# Morpheus_MCU.net
KiCad netlist of a schematic drawn in Altium Designer
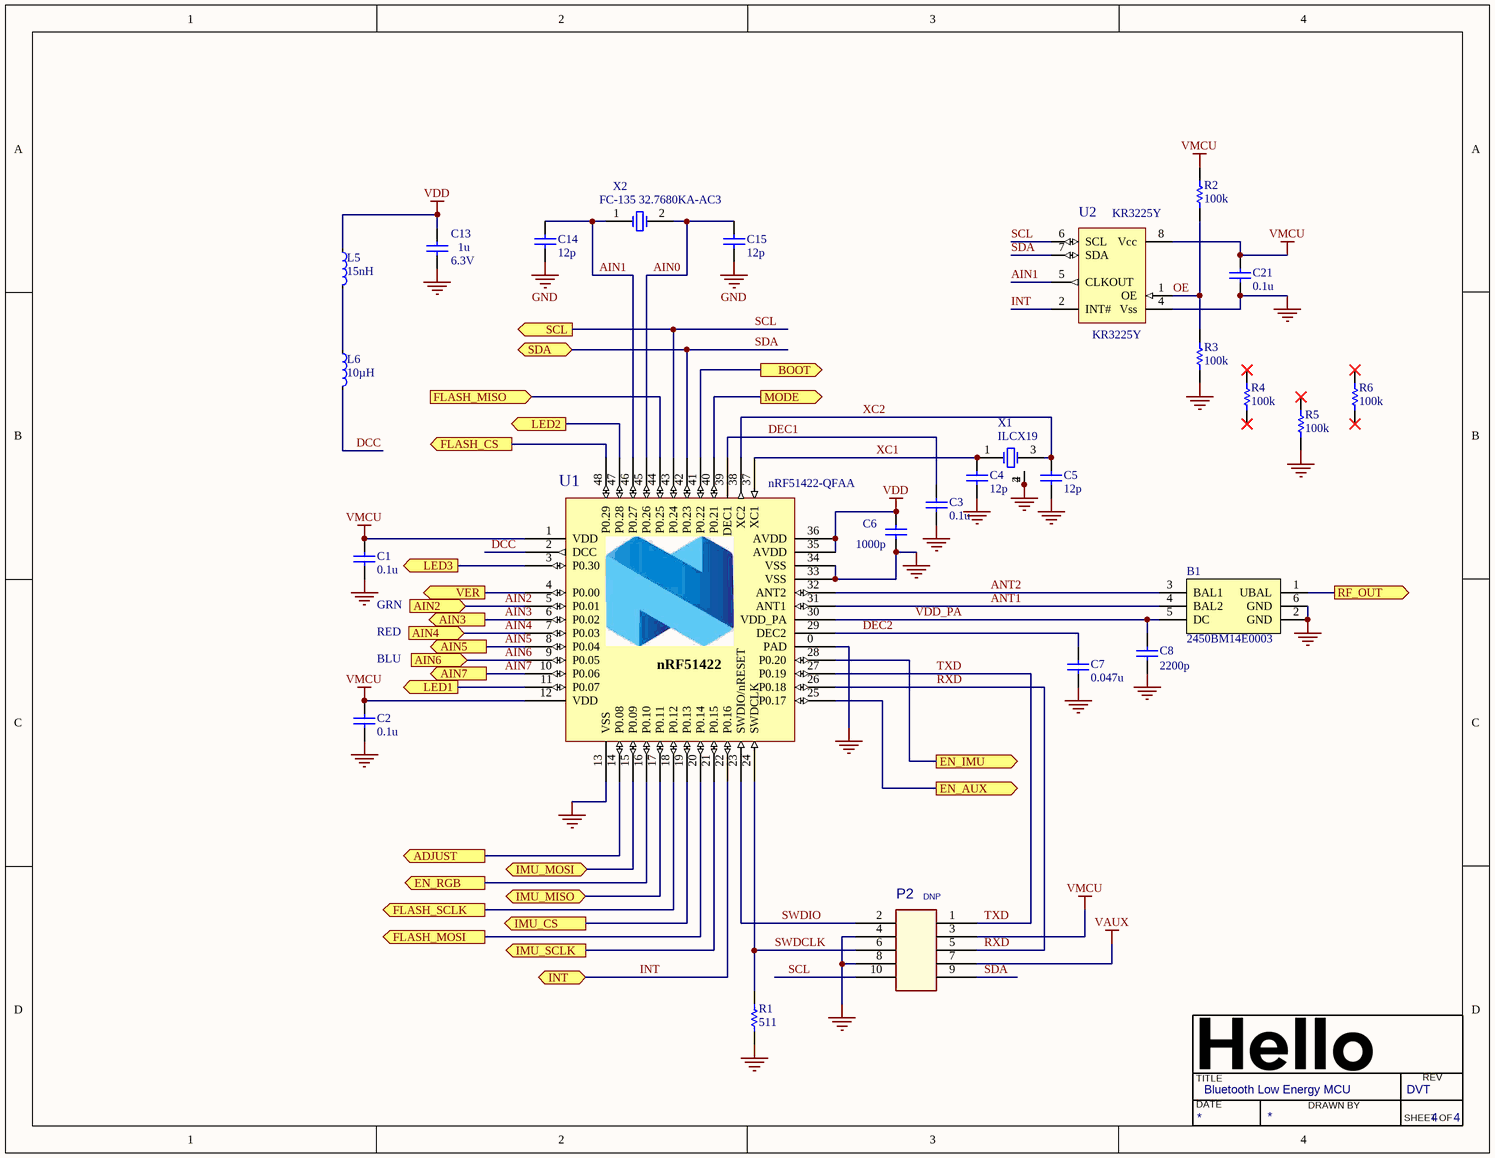
[diagram p0: Morpheus_MCU.SchDoc]

(export (version "E")
  (design (tool "Eeschema 10.0.6"))
  (components
    (comp (ref "B1")
      (value "2450BM14E0003")
      (footprint "DFN50P160X80X70-6N")
      (description "2.45 GHz Impedance Matched Balun-Filter")
      (libsource (lib "HelloDVT") (part "2450BM14E0003"))
    )
    (comp (ref "C1")
      (value "0.1u")
      (footprint "CAP0402_SENSE_DVT")
      (description "Chip capacitor")
      (fields (field (name "TOLERANCE") "10%") (field (name "VOLTAGE") "50V"))
      (libsource (lib "Hello") (part "C_0.1u_10_50_X7R_0402"))
    )
    (comp (ref "C2")
      (value "0.1u")
      (footprint "CAP0402_SENSE_DVT")
      (description "Chip capacitor")
      (fields (field (name "TOLERANCE") "10%") (field (name "VOLTAGE") "50V"))
      (libsource (lib "Hello") (part "C_0.1u_10_50_X7R_0402"))
    )
    (comp (ref "C3")
      (value "0.1u")
      (footprint "CAP0402_SENSE_DVT")
      (description "Chip capacitor")
      (fields (field (name "TOLERANCE") "10%") (field (name "VOLTAGE") "50V"))
      (libsource (lib "Hello") (part "C_0.1u_10_50_X7R_0402"))
    )
    (comp (ref "C4")
      (value "12p")
      (footprint "CAP0402_SENSE_DVT")
      (description "Chip capacitor")
      (fields (field (name "TOLERANCE") "5%") (field (name "VOLTAGE") "50V"))
      (libsource (lib "Hello") (part "C_12p_5_50_C0G_0402"))
    )
    (comp (ref "C5")
      (value "12p")
      (footprint "CAP0402_SENSE_DVT")
      (description "Chip capacitor")
      (fields (field (name "TOLERANCE") "5%") (field (name "VOLTAGE") "50V"))
      (libsource (lib "Hello") (part "C_12p_5_50_C0G_0402"))
    )
    (comp (ref "C6")
      (value "1000p")
      (footprint "CAP0402_SENSE_DVT")
      (description "Chip capacitor")
      (fields (field (name "TOLERANCE") "10%") (field (name "VOLTAGE") "25V"))
      (libsource (lib "Hello") (part "C_1000p_10_25_X7R_0201"))
    )
    (comp (ref "C7")
      (value "0.047u")
      (footprint "CAP0402_SENSE_DVT")
      (description "Chip capacitor")
      (fields (field (name "TOLERANCE") "10%") (field (name "VOLTAGE") "16V"))
      (libsource (lib "Hello") (part "C_0.047u_10_16_X5R_0201"))
    )
    (comp (ref "C8")
      (value "2200p")
      (footprint "CAP0402_SENSE_DVT")
      (description "Chip capacitor")
      (fields (field (name "TOLERANCE") "5 %") (field (name "VOLTAGE") "16V"))
      (libsource (lib "Hello") (part "C_2200p_5_16_X7R_0201"))
    )
    (comp (ref "C13")
      (value "1u")
      (footprint "CAP0402_SENSE_DVT")
      (description "Chip capacitor")
      (fields (field (name "TOLERANCE") "10%") (field (name "VOLTAGE") "6.3V"))
      (libsource (lib "Hello") (part "C_1u_10_6.3_X5R_0402"))
    )
    (comp (ref "C14")
      (value "12p")
      (footprint "CAP0402_SENSE_DVT")
      (description "Chip capacitor")
      (fields (field (name "TOLERANCE") "5%") (field (name "VOLTAGE") "50V"))
      (libsource (lib "Hello") (part "C_12p_5_50_C0G_0402"))
    )
    (comp (ref "C15")
      (value "12p")
      (footprint "CAP0402_SENSE_DVT")
      (description "Chip capacitor")
      (fields (field (name "TOLERANCE") "5%") (field (name "VOLTAGE") "50V"))
      (libsource (lib "Hello") (part "C_12p_5_50_C0G_0402"))
    )
    (comp (ref "C21")
      (value "0.1u")
      (footprint "CAP0402_SENSE_DVT")
      (description "Chip capacitor")
      (fields (field (name "TOLERANCE") "10%") (field (name "VOLTAGE") "50V"))
      (libsource (lib "Hello") (part "C_0.1u_10_50_X7R_0402"))
    )
    (comp (ref "L5")
      (value "15nH")
      (footprint "INDC1005X04L")
      (description "Inductor, 320mA, ±5%")
      (fields
        (field (name "PART NUMBER") "L0402-15n")
        (field (name "MANUFACTURER") "Taiyo Yuden")
        (field (name "PUBLISHER") "Nordic Semiconductor")
      )
      (libsource (lib "Nordic Passive DB") (part "IND"))
    )
    (comp (ref "L6")
      (value "10µH")
      (footprint "INDC1608X06L")
      (description "Inductor, 80mA, ±10%")
      (fields
        (field (name "PART NUMBER") "L0603-10µ")
        (field (name "MANUFACTURER") "Taiyo Yuden")
        (field (name "PUBLISHER") "Nordic Semiconductor")
      )
      (libsource (lib "Nordic Passive DB") (part "IND"))
    )
    (comp (ref "P2")
      (value "DNP")
      (footprint "HDR1.27-2X5-N")
      (libsource (lib "Morpheus_LED") (part "CON10A"))
    )
    (comp (ref "R1")
      (value "511")
      (footprint "RES0402_SENSE_DVT")
      (description "Chip Resistor")
      (fields (field (name "TOLERANCE") "1 %") (field (name "POWER") "0.1 W"))
      (libsource (lib "Hello") (part "R_511_1_0.1_0402"))
    )
    (comp (ref "R2")
      (value "100k")
      (footprint "RES0402_SENSE_DVT")
      (description "Chip Resistor")
      (fields (field (name "TOLERANCE") "1 %") (field (name "POWER") "0.1 W"))
      (libsource (lib "Hello") (part "R_100k_1_0.1_0402"))
    )
    (comp (ref "R3")
      (value "100k")
      (footprint "RES0402_SENSE_DVT")
      (description "Chip Resistor")
      (fields (field (name "TOLERANCE") "1 %") (field (name "POWER") "0.1 W"))
      (libsource (lib "Hello") (part "R_100k_1_0.1_0402"))
    )
    (comp (ref "R4")
      (value "100k")
      (footprint "RES0402_SENSE_DVT")
      (description "Chip Resistor")
      (fields (field (name "TOLERANCE") "1 %") (field (name "POWER") "0.1 W"))
      (libsource (lib "Hello") (part "R_100k_1_0.1_0402"))
    )
    (comp (ref "R5")
      (value "100k")
      (footprint "RES0402_SENSE_DVT")
      (description "Chip Resistor")
      (fields (field (name "TOLERANCE") "1 %") (field (name "POWER") "0.1 W"))
      (libsource (lib "Hello") (part "R_100k_1_0.1_0402"))
    )
    (comp (ref "R6")
      (value "100k")
      (footprint "RES0402_SENSE_DVT")
      (description "Chip Resistor")
      (fields (field (name "TOLERANCE") "1 %") (field (name "POWER") "0.1 W"))
      (libsource (lib "Hello") (part "R_100k_1_0.1_0402"))
    )
    (comp (ref "U1")
      (value "nRF51422-QFAA")
      (footprint "VQFN40P600X600X100-48")
      (description "Multi-protocol Bluetooth Low Energy, ANT and 2.4GHz proprietary system-on-chip")
      (libsource (lib "Hello") (part "nRF51422_QFAA"))
    )
    (comp (ref "U2")
      (value "KR3225Y")
      (footprint "8-CLCC-KYOCERO")
      (description "Kyocero I2C RTC w/ Crystal")
      (fields (field (name "PN") "KR3225Y"))
      (libsource (lib "Smith_top") (part "KR3225Y32768DGR"))
    )
    (comp (ref "X1")
      (value "ILCX19")
      (footprint "ILCX19")
      (description "ILSI ILCX19 Crystal Oscillator")
      (libsource (lib "Smith_top") (part "ILCX19"))
    )
    (comp (ref "X2")
      (value "FC-135 32.7680KA-AC3")
      (footprint "Epson_FC-135")
      (description "Epson 32kHz crystal, 9pF")
      (libsource (lib "Hello") (part "Espon_FC-135 32.7680KA-AC3"))
    )
  )
  (nets
    (net (code "1") (name "/ADJUST") (class "Default")
      (node (ref "U1") (pin "14") (pinfunction "P0.08_14") (pintype "bidirectional"))
    )
    (net (code "2") (name "/AIN0") (class "Default")
      (node (ref "C15") (pin "2") (pinfunction "2_2") (pintype "passive"))
      (node (ref "U1") (pin "45") (pinfunction "P0.26_45") (pintype "bidirectional"))
      (node (ref "X2") (pin "2") (pinfunction "2_2") (pintype "passive"))
    )
    (net (code "3") (name "/AIN1") (class "Default")
      (node (ref "C14") (pin "2") (pinfunction "2_2") (pintype "passive"))
      (node (ref "U1") (pin "46") (pinfunction "P0.27_46") (pintype "bidirectional"))
      (node (ref "U2") (pin "5") (pinfunction "CLKOUT_5") (pintype "output"))
      (node (ref "X2") (pin "1") (pinfunction "1_1") (pintype "passive"))
    )
    (net (code "4") (name "/AIN2") (class "Default")
      (node (ref "U1") (pin "5") (pinfunction "P0.01_5") (pintype "bidirectional"))
    )
    (net (code "5") (name "/AIN3") (class "Default")
      (node (ref "U1") (pin "6") (pinfunction "P0.02_6") (pintype "bidirectional"))
    )
    (net (code "6") (name "/AIN4") (class "Default")
      (node (ref "U1") (pin "7") (pinfunction "P0.03_7") (pintype "bidirectional"))
    )
    (net (code "7") (name "/AIN5") (class "Default")
      (node (ref "U1") (pin "8") (pinfunction "P0.04_8") (pintype "bidirectional"))
    )
    (net (code "8") (name "/AIN6") (class "Default")
      (node (ref "U1") (pin "9") (pinfunction "P0.05_9") (pintype "bidirectional"))
    )
    (net (code "9") (name "/AIN7") (class "Default")
      (node (ref "U1") (pin "10") (pinfunction "P0.06_10") (pintype "bidirectional"))
    )
    (net (code "10") (name "/ANT1") (class "Default")
      (node (ref "B1") (pin "4") (pinfunction "BAL2_4") (pintype "passive"))
      (node (ref "U1") (pin "31") (pinfunction "ANT1_31") (pintype "bidirectional"))
    )
    (net (code "11") (name "/ANT2") (class "Default")
      (node (ref "B1") (pin "3") (pinfunction "BAL1_3") (pintype "passive"))
      (node (ref "U1") (pin "32") (pinfunction "ANT2_32") (pintype "bidirectional"))
    )
    (net (code "12") (name "/BOOT") (class "Default")
      (node (ref "U1") (pin "41") (pinfunction "P0.22_41") (pintype "bidirectional"))
    )
    (net (code "13") (name "/DCC") (class "Default")
      (node (ref "L6") (pin "2") (pinfunction "2_2") (pintype "passive"))
      (node (ref "U1") (pin "2") (pinfunction "DCC_2") (pintype "output"))
    )
    (net (code "14") (name "/DEC1") (class "Default")
      (node (ref "C3") (pin "2") (pinfunction "2_2") (pintype "passive"))
      (node (ref "U1") (pin "39") (pinfunction "DEC1_39") (pintype "power_in"))
    )
    (net (code "15") (name "/DEC2") (class "Default")
      (node (ref "C7") (pin "2") (pinfunction "2_2") (pintype "passive"))
      (node (ref "U1") (pin "29") (pinfunction "DEC2_29") (pintype "power_in"))
    )
    (net (code "16") (name "/EN_AUX") (class "Default")
      (node (ref "U1") (pin "25") (pinfunction "P0.17_25") (pintype "bidirectional"))
    )
    (net (code "17") (name "/EN_IMU") (class "Default")
      (node (ref "U1") (pin "28") (pinfunction "P0.20_28") (pintype "bidirectional"))
    )
    (net (code "18") (name "/EN_RGB") (class "Default")
      (node (ref "U1") (pin "16") (pinfunction "P0.10_16") (pintype "bidirectional"))
    )
    (net (code "19") (name "/FLASH_CS") (class "Default")
      (node (ref "U1") (pin "48") (pinfunction "P0.29_48") (pintype "bidirectional"))
    )
    (net (code "20") (name "/FLASH_MISO") (class "Default")
      (node (ref "U1") (pin "44") (pinfunction "P0.25_44") (pintype "bidirectional"))
    )
    (net (code "21") (name "/FLASH_MOSI") (class "Default")
      (node (ref "U1") (pin "20") (pinfunction "P0.14_20") (pintype "bidirectional"))
    )
    (net (code "22") (name "/FLASH_SCLK") (class "Default")
      (node (ref "U1") (pin "18") (pinfunction "P0.12_18") (pintype "bidirectional"))
    )
    (net (code "23") (name "/IMU_CS") (class "Default")
      (node (ref "U1") (pin "19") (pinfunction "P0.13_19") (pintype "bidirectional"))
    )
    (net (code "24") (name "/IMU_MISO") (class "Default")
      (node (ref "U1") (pin "17") (pinfunction "P0.11_17") (pintype "bidirectional"))
    )
    (net (code "25") (name "/IMU_MOSI") (class "Default")
      (node (ref "U1") (pin "15") (pinfunction "P0.09_15") (pintype "bidirectional"))
    )
    (net (code "26") (name "/IMU_SCLK") (class "Default")
      (node (ref "U1") (pin "21") (pinfunction "P0.15_21") (pintype "bidirectional"))
    )
    (net (code "27") (name "/INT") (class "Default")
      (node (ref "U1") (pin "22") (pinfunction "P0.16_22") (pintype "bidirectional"))
      (node (ref "U2") (pin "2") (pinfunction "INT#_2") (pintype "open_emitter"))
    )
    (net (code "28") (name "/LED1") (class "Default")
      (node (ref "U1") (pin "11") (pinfunction "P0.07_11") (pintype "bidirectional"))
    )
    (net (code "29") (name "/LED2") (class "Default")
      (node (ref "U1") (pin "47") (pinfunction "P0.28_47") (pintype "bidirectional"))
    )
    (net (code "30") (name "/LED3") (class "Default")
      (node (ref "U1") (pin "3") (pinfunction "P0.30_3") (pintype "bidirectional"))
    )
    (net (code "31") (name "/MODE") (class "Default")
      (node (ref "U1") (pin "40") (pinfunction "P0.21_40") (pintype "bidirectional"))
    )
    (net (code "32") (name "/OE") (class "Default")
      (node (ref "R2") (pin "1") (pinfunction "1_1") (pintype "passive"))
      (node (ref "R3") (pin "2") (pinfunction "2_2") (pintype "passive"))
      (node (ref "U2") (pin "1") (pinfunction "OE_1") (pintype "input"))
    )
    (net (code "33") (name "/RF_OUT") (class "Default")
      (node (ref "B1") (pin "1") (pinfunction "UBAL_1") (pintype "passive"))
    )
    (net (code "34") (name "/RXD") (class "Default")
      (node (ref "P2") (pin "5") (pinfunction "5_5") (pintype "passive"))
      (node (ref "U1") (pin "26") (pinfunction "P0.18_26") (pintype "bidirectional"))
    )
    (net (code "35") (name "/SCL") (class "Default")
      (node (ref "P2") (pin "10") (pinfunction "10_10") (pintype "passive"))
      (node (ref "U1") (pin "43") (pinfunction "P0.24_43") (pintype "bidirectional"))
      (node (ref "U2") (pin "6") (pinfunction "SCL_6") (pintype "bidirectional"))
    )
    (net (code "36") (name "/SDA") (class "Default")
      (node (ref "P2") (pin "9") (pinfunction "9_9") (pintype "passive"))
      (node (ref "U1") (pin "42") (pinfunction "P0.23_42") (pintype "bidirectional"))
      (node (ref "U2") (pin "7") (pinfunction "SDA_7") (pintype "bidirectional"))
    )
    (net (code "37") (name "/SWDCLK") (class "Default")
      (node (ref "P2") (pin "6") (pinfunction "6_6") (pintype "passive"))
      (node (ref "R1") (pin "2") (pinfunction "2_2") (pintype "passive"))
      (node (ref "U1") (pin "24") (pinfunction "SWDCLK_24") (pintype "input"))
    )
    (net (code "38") (name "/SWDIO") (class "Default")
      (node (ref "P2") (pin "2") (pinfunction "2_2") (pintype "passive"))
      (node (ref "U1") (pin "23") (pinfunction "SWDIO/nRESET_23") (pintype "input"))
    )
    (net (code "39") (name "/TXD") (class "Default")
      (node (ref "P2") (pin "1") (pinfunction "1_1") (pintype "passive"))
      (node (ref "U1") (pin "27") (pinfunction "P0.19_27") (pintype "bidirectional"))
    )
    (net (code "40") (name "/VDD_PA") (class "Default")
      (node (ref "B1") (pin "5") (pinfunction "DC_5") (pintype "passive"))
      (node (ref "C8") (pin "2") (pinfunction "2_2") (pintype "passive"))
      (node (ref "U1") (pin "30") (pinfunction "VDD_PA_30") (pintype "power_in"))
    )
    (net (code "41") (name "/VER") (class "Default")
      (node (ref "U1") (pin "4") (pinfunction "P0.00_4") (pintype "bidirectional"))
    )
    (net (code "42") (name "/XC1") (class "Default")
      (node (ref "C4") (pin "2") (pinfunction "2_2") (pintype "passive"))
      (node (ref "U1") (pin "37") (pinfunction "XC1_37") (pintype "input"))
      (node (ref "X1") (pin "1") (pinfunction "XTAL1_1") (pintype "passive"))
    )
    (net (code "43") (name "/XC2") (class "Default")
      (node (ref "C5") (pin "2") (pinfunction "2_2") (pintype "passive"))
      (node (ref "U1") (pin "38") (pinfunction "XC2_38") (pintype "output"))
      (node (ref "X1") (pin "3") (pinfunction "XTAL2_3") (pintype "passive"))
    )
    (net (code "44") (name "GND") (class "Default")
      (node (ref "B1") (pin "2") (pinfunction "GND_2") (pintype "passive"))
      (node (ref "B1") (pin "6") (pinfunction "GND_6") (pintype "power_in"))
      (node (ref "C1") (pin "1") (pinfunction "1_1") (pintype "passive"))
      (node (ref "C13") (pin "1") (pinfunction "1_1") (pintype "passive"))
      (node (ref "C14") (pin "1") (pinfunction "1_1") (pintype "passive"))
      (node (ref "C15") (pin "1") (pinfunction "1_1") (pintype "passive"))
      (node (ref "C2") (pin "1") (pinfunction "1_1") (pintype "passive"))
      (node (ref "C21") (pin "1") (pinfunction "1_1") (pintype "passive"))
      (node (ref "C3") (pin "1") (pinfunction "1_1") (pintype "passive"))
      (node (ref "C4") (pin "1") (pinfunction "1_1") (pintype "passive"))
      (node (ref "C5") (pin "1") (pinfunction "1_1") (pintype "passive"))
      (node (ref "C6") (pin "1") (pinfunction "1_1") (pintype "passive"))
      (node (ref "C7") (pin "1") (pinfunction "1_1") (pintype "passive"))
      (node (ref "C8") (pin "1") (pinfunction "1_1") (pintype "passive"))
      (node (ref "P2") (pin "4") (pinfunction "4_4") (pintype "passive"))
      (node (ref "P2") (pin "8") (pinfunction "8_8") (pintype "passive"))
      (node (ref "R1") (pin "1") (pinfunction "1_1") (pintype "passive"))
      (node (ref "R3") (pin "1") (pinfunction "1_1") (pintype "passive"))
      (node (ref "R5") (pin "1") (pinfunction "1_1") (pintype "passive"))
      (node (ref "U1") (pin "0") (pinfunction "PAD_0") (pintype "power_in"))
      (node (ref "U1") (pin "13") (pinfunction "VSS_13") (pintype "power_in"))
      (node (ref "U1") (pin "33") (pinfunction "VSS_33") (pintype "power_in"))
      (node (ref "U1") (pin "34") (pinfunction "VSS_34") (pintype "power_in"))
      (node (ref "U2") (pin "4") (pinfunction "Vss_4") (pintype "power_in"))
      (node (ref "X1") (pin "2") (pinfunction "GND1_2") (pintype "passive"))
      (node (ref "X1") (pin "4") (pinfunction "XTAL2_4") (pintype "passive"))
    )
    (net (code "45") (name "Net-(L5-Pad2)") (class "Default")
      (node (ref "L5") (pin "2") (pinfunction "2_2") (pintype "passive"))
      (node (ref "L6") (pin "1") (pinfunction "1_1") (pintype "passive"))
    )
    (net (code "46") (name "VAUX") (class "Default")
      (node (ref "P2") (pin "7") (pinfunction "7_7") (pintype "passive"))
    )
    (net (code "47") (name "VDD") (class "Default")
      (node (ref "C13") (pin "2") (pinfunction "2_2") (pintype "passive"))
      (node (ref "C6") (pin "2") (pinfunction "2_2") (pintype "passive"))
      (node (ref "L5") (pin "1") (pinfunction "1_1") (pintype "passive"))
      (node (ref "U1") (pin "35") (pinfunction "AVDD_35") (pintype "power_in"))
      (node (ref "U1") (pin "36") (pinfunction "AVDD_36") (pintype "power_in"))
    )
    (net (code "48") (name "VMCU") (class "Default")
      (node (ref "C1") (pin "2") (pinfunction "2_2") (pintype "passive"))
      (node (ref "C2") (pin "2") (pinfunction "2_2") (pintype "passive"))
      (node (ref "C21") (pin "2") (pinfunction "2_2") (pintype "passive"))
      (node (ref "P2") (pin "3") (pinfunction "3_3") (pintype "passive"))
      (node (ref "R2") (pin "2") (pinfunction "2_2") (pintype "passive"))
      (node (ref "U1") (pin "1") (pinfunction "VDD_1") (pintype "power_in"))
      (node (ref "U1") (pin "12") (pinfunction "VDD_12") (pintype "power_in"))
      (node (ref "U2") (pin "8") (pinfunction "Vcc_8") (pintype "power_in"))
    )
    (net (code "49") (name "unconnected-(R4-Pad1)") (class "Default")
      (node (ref "R4") (pin "1") (pinfunction "1_1") (pintype "passive+no_connect"))
    )
    (net (code "50") (name "unconnected-(R4-Pad2)") (class "Default")
      (node (ref "R4") (pin "2") (pinfunction "2_2") (pintype "passive+no_connect"))
    )
    (net (code "51") (name "unconnected-(R5-Pad2)") (class "Default")
      (node (ref "R5") (pin "2") (pinfunction "2_2") (pintype "passive+no_connect"))
    )
    (net (code "52") (name "unconnected-(R6-Pad1)") (class "Default")
      (node (ref "R6") (pin "1") (pinfunction "1_1") (pintype "passive+no_connect"))
    )
    (net (code "53") (name "unconnected-(R6-Pad2)") (class "Default")
      (node (ref "R6") (pin "2") (pinfunction "2_2") (pintype "passive+no_connect"))
    )
    (net (code "54") (name "unconnected-(U2-NC-Pad4)") (class "Default")
      (node (ref "U2") (pin "4") (pinfunction "NC_4") (pintype "passive"))
    )
    (net (code "55") (name "unconnected-(U2-NC-Pad7)") (class "Default")
      (node (ref "U2") (pin "7") (pinfunction "NC_7") (pintype "passive"))
    )
  )
)
